# dotstar-stick-mk-1_0.net
KiCad netlist of a schematic drawn in EAGLE
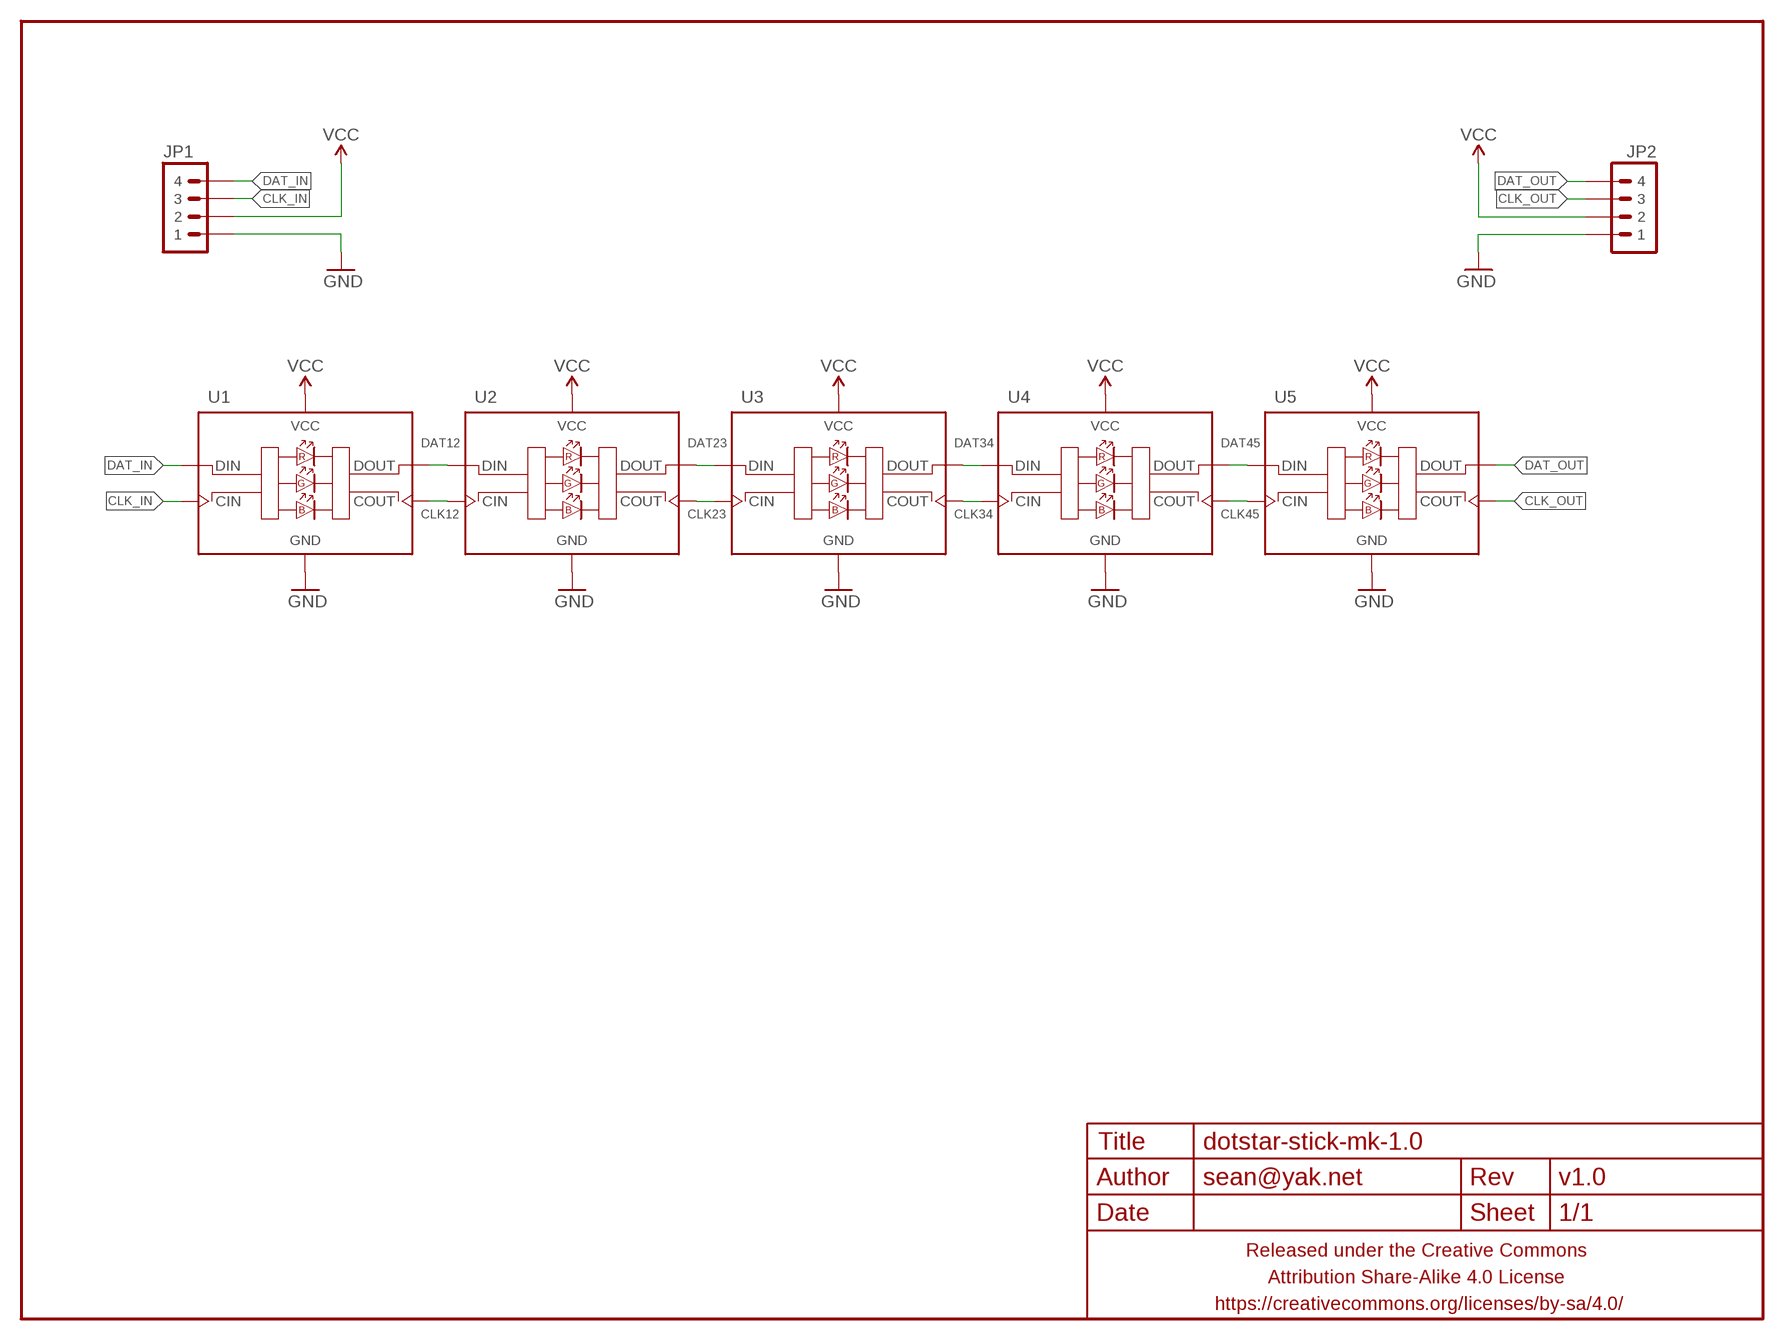
[diagram p0: schematic, sheet 1]

(export (version "E")
  (design (tool "Eeschema 10.0.6"))
  (components
    (comp (ref "FRAME1")
      (value "FRAME-LETTERNO_PACKAGE")
      (footprint "eagle-import:DUMMY")
      (fields (field (name "DESIGNER") "sean@yak.net") (field (name "VERSION") "v1.0"))
      (libsource (lib "eagle-import") (part "FRAME-LETTERNO_PACKAGE"))
    )
    (comp (ref "JP1")
      (value "M04PTH-2MM-CENTERED")
      (footprint "eagle-import:1X04-2MM-CENTERED")
      (libsource (lib "eagle-import") (part "M04PTH-2MM-CENTERED"))
    )
    (comp (ref "JP2")
      (value "M04PTH-2MM-CENTERED")
      (footprint "eagle-import:1X04-2MM-CENTERED")
      (libsource (lib "eagle-import") (part "M04PTH-2MM-CENTERED"))
    )
    (comp (ref "U1")
      (value "DOTSTARAPA102-5050")
      (footprint "eagle-import:LED-5050")
      (libsource (lib "eagle-import") (part "DOTSTARAPA102-5050"))
    )
    (comp (ref "U2")
      (value "DOTSTARAPA102-5050")
      (footprint "eagle-import:LED-5050")
      (libsource (lib "eagle-import") (part "DOTSTARAPA102-5050"))
    )
    (comp (ref "U3")
      (value "DOTSTARAPA102-5050")
      (footprint "eagle-import:LED-5050")
      (libsource (lib "eagle-import") (part "DOTSTARAPA102-5050"))
    )
    (comp (ref "U4")
      (value "DOTSTARAPA102-5050")
      (footprint "eagle-import:LED-5050")
      (libsource (lib "eagle-import") (part "DOTSTARAPA102-5050"))
    )
    (comp (ref "U5")
      (value "DOTSTARAPA102-5050")
      (footprint "eagle-import:LED-5050")
      (libsource (lib "eagle-import") (part "DOTSTARAPA102-5050"))
    )
  )
  (nets
    (net (code "1") (name "/CLK12") (class "Default")
      (node (ref "U1") (pin "5") (pinfunction "COUT_5") (pintype "bidirectional"))
      (node (ref "U2") (pin "2") (pinfunction "CIN_2") (pintype "bidirectional"))
    )
    (net (code "2") (name "/CLK23") (class "Default")
      (node (ref "U2") (pin "5") (pinfunction "COUT_5") (pintype "bidirectional"))
      (node (ref "U3") (pin "2") (pinfunction "CIN_2") (pintype "bidirectional"))
    )
    (net (code "3") (name "/CLK34") (class "Default")
      (node (ref "U3") (pin "5") (pinfunction "COUT_5") (pintype "bidirectional"))
      (node (ref "U4") (pin "2") (pinfunction "CIN_2") (pintype "bidirectional"))
    )
    (net (code "4") (name "/CLK45") (class "Default")
      (node (ref "U4") (pin "5") (pinfunction "COUT_5") (pintype "bidirectional"))
      (node (ref "U5") (pin "2") (pinfunction "CIN_2") (pintype "bidirectional"))
    )
    (net (code "5") (name "/DAT12") (class "Default")
      (node (ref "U1") (pin "6") (pinfunction "DOUT_6") (pintype "bidirectional"))
      (node (ref "U2") (pin "1") (pinfunction "DIN_1") (pintype "bidirectional"))
    )
    (net (code "6") (name "/DAT23") (class "Default")
      (node (ref "U2") (pin "6") (pinfunction "DOUT_6") (pintype "bidirectional"))
      (node (ref "U3") (pin "1") (pinfunction "DIN_1") (pintype "bidirectional"))
    )
    (net (code "7") (name "/DAT34") (class "Default")
      (node (ref "U3") (pin "6") (pinfunction "DOUT_6") (pintype "bidirectional"))
      (node (ref "U4") (pin "1") (pinfunction "DIN_1") (pintype "bidirectional"))
    )
    (net (code "8") (name "/DAT45") (class "Default")
      (node (ref "U4") (pin "6") (pinfunction "DOUT_6") (pintype "bidirectional"))
      (node (ref "U5") (pin "1") (pinfunction "DIN_1") (pintype "bidirectional"))
    )
    (net (code "9") (name "CLK_IN") (class "Default")
      (node (ref "JP1") (pin "3") (pinfunction "3_3") (pintype "passive"))
      (node (ref "U1") (pin "2") (pinfunction "CIN_2") (pintype "bidirectional"))
    )
    (net (code "10") (name "CLK_OUT") (class "Default")
      (node (ref "JP2") (pin "3") (pinfunction "3_3") (pintype "passive"))
      (node (ref "U5") (pin "5") (pinfunction "COUT_5") (pintype "bidirectional"))
    )
    (net (code "11") (name "DAT_IN") (class "Default")
      (node (ref "JP1") (pin "4") (pinfunction "4_4") (pintype "passive"))
      (node (ref "U1") (pin "1") (pinfunction "DIN_1") (pintype "bidirectional"))
    )
    (net (code "12") (name "DAT_OUT") (class "Default")
      (node (ref "JP2") (pin "4") (pinfunction "4_4") (pintype "passive"))
      (node (ref "U5") (pin "6") (pinfunction "DOUT_6") (pintype "bidirectional"))
    )
    (net (code "13") (name "GND") (class "Default")
      (node (ref "JP1") (pin "1") (pinfunction "1_1") (pintype "passive"))
      (node (ref "JP2") (pin "1") (pinfunction "1_1") (pintype "passive"))
      (node (ref "U1") (pin "3") (pinfunction "GND_3") (pintype "bidirectional"))
      (node (ref "U2") (pin "3") (pinfunction "GND_3") (pintype "bidirectional"))
      (node (ref "U3") (pin "3") (pinfunction "GND_3") (pintype "bidirectional"))
      (node (ref "U4") (pin "3") (pinfunction "GND_3") (pintype "bidirectional"))
      (node (ref "U5") (pin "3") (pinfunction "GND_3") (pintype "bidirectional"))
    )
    (net (code "14") (name "VCC") (class "Default")
      (node (ref "JP1") (pin "2") (pinfunction "2_2") (pintype "passive"))
      (node (ref "JP2") (pin "2") (pinfunction "2_2") (pintype "passive"))
      (node (ref "U1") (pin "4") (pinfunction "VCC_4") (pintype "bidirectional"))
      (node (ref "U2") (pin "4") (pinfunction "VCC_4") (pintype "bidirectional"))
      (node (ref "U3") (pin "4") (pinfunction "VCC_4") (pintype "bidirectional"))
      (node (ref "U4") (pin "4") (pinfunction "VCC_4") (pintype "bidirectional"))
      (node (ref "U5") (pin "4") (pinfunction "VCC_4") (pintype "bidirectional"))
    )
  )
)
